# 10_BOOT.net
KiCad netlist of a schematic drawn in Altium Designer
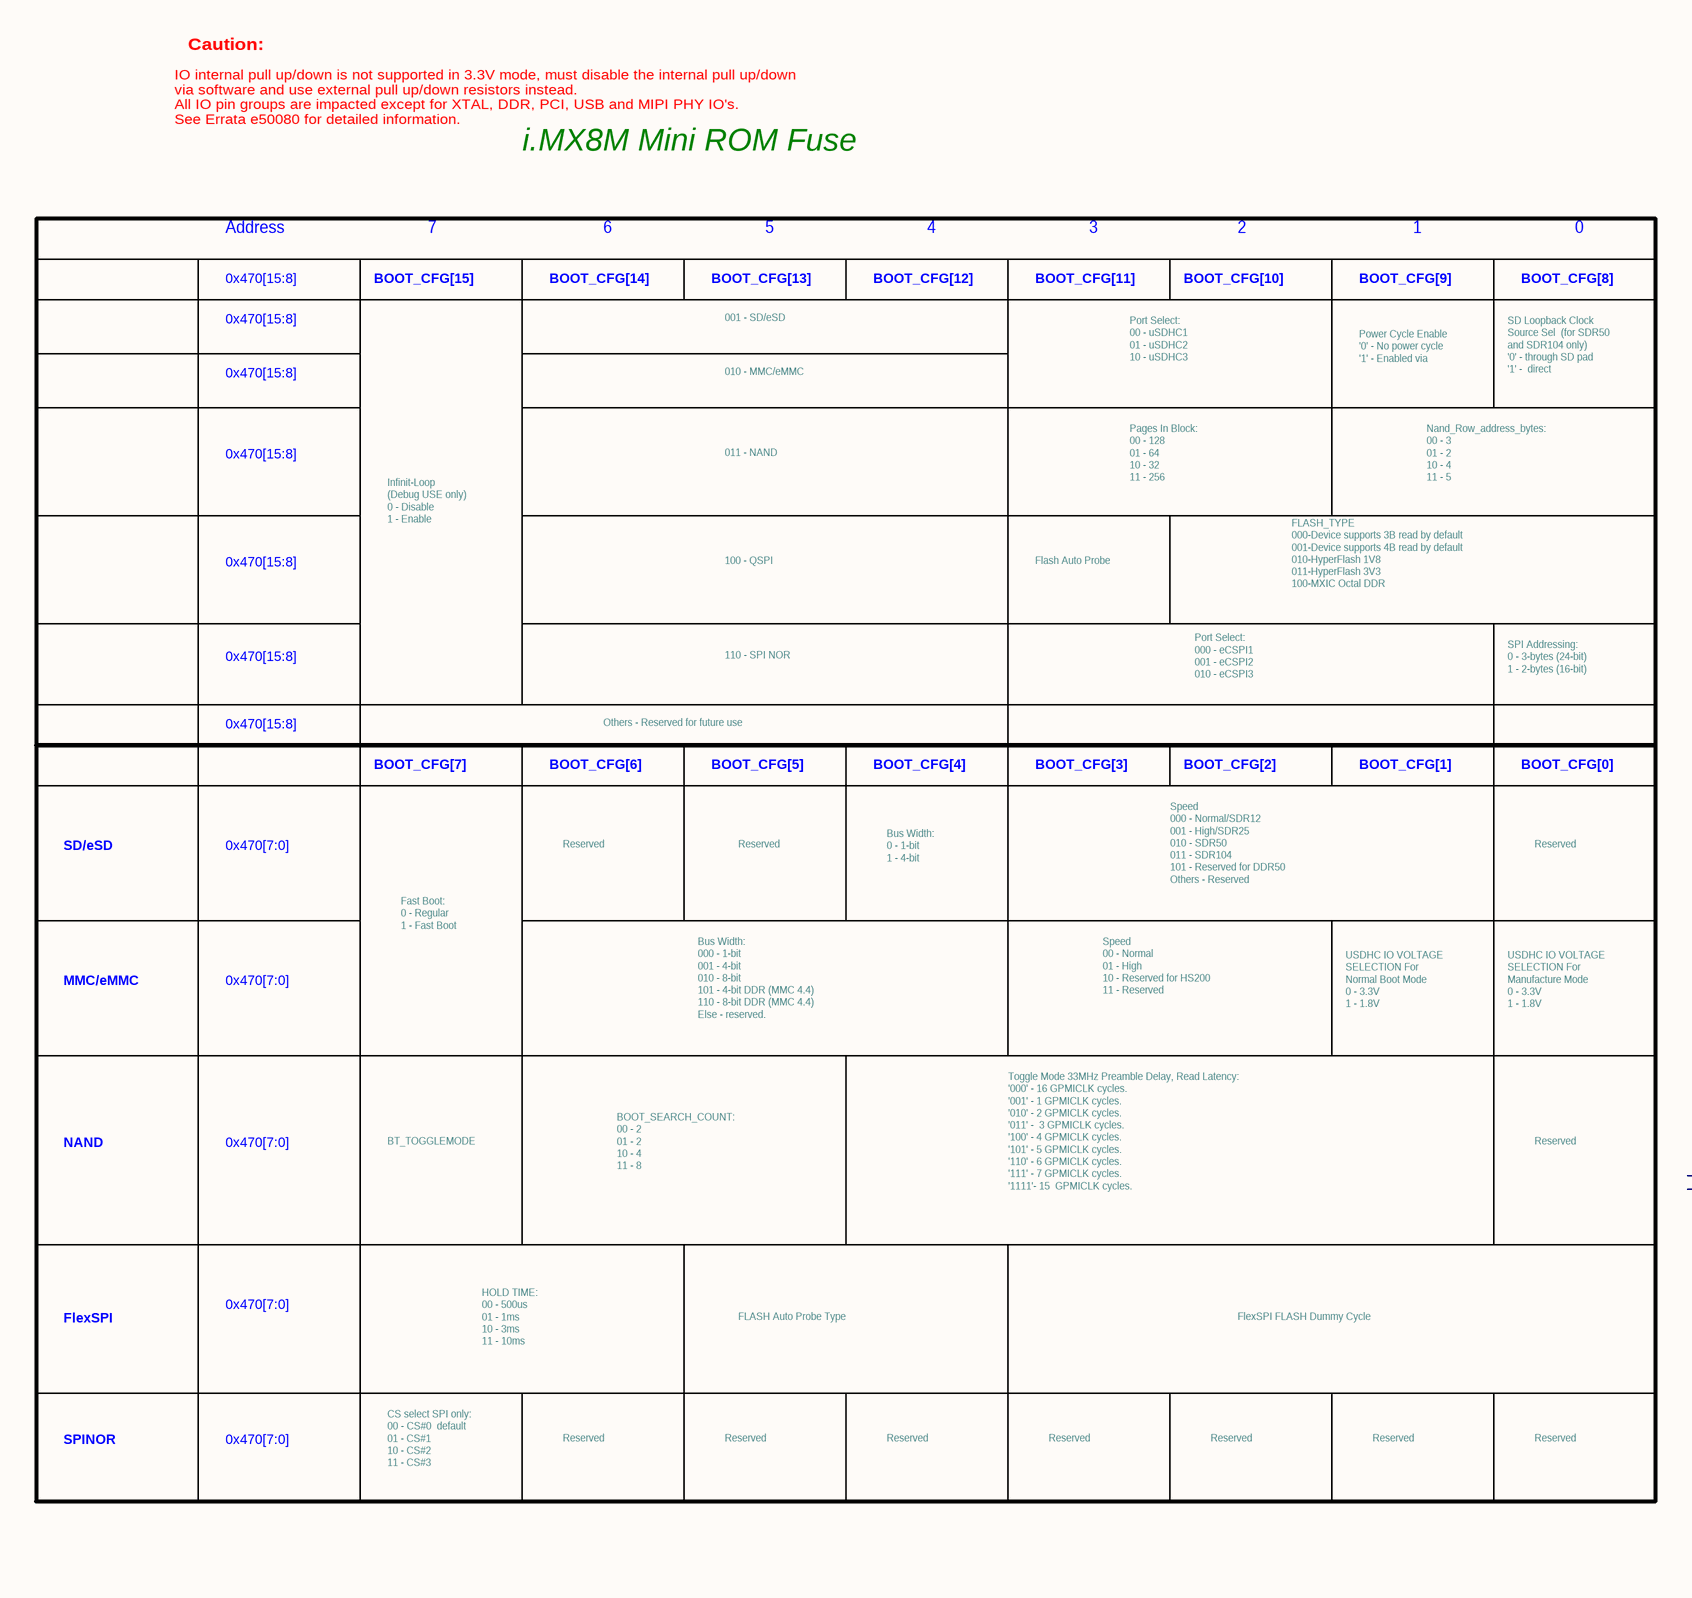
[diagram p0: 10 BOOT.SchDoc, left]
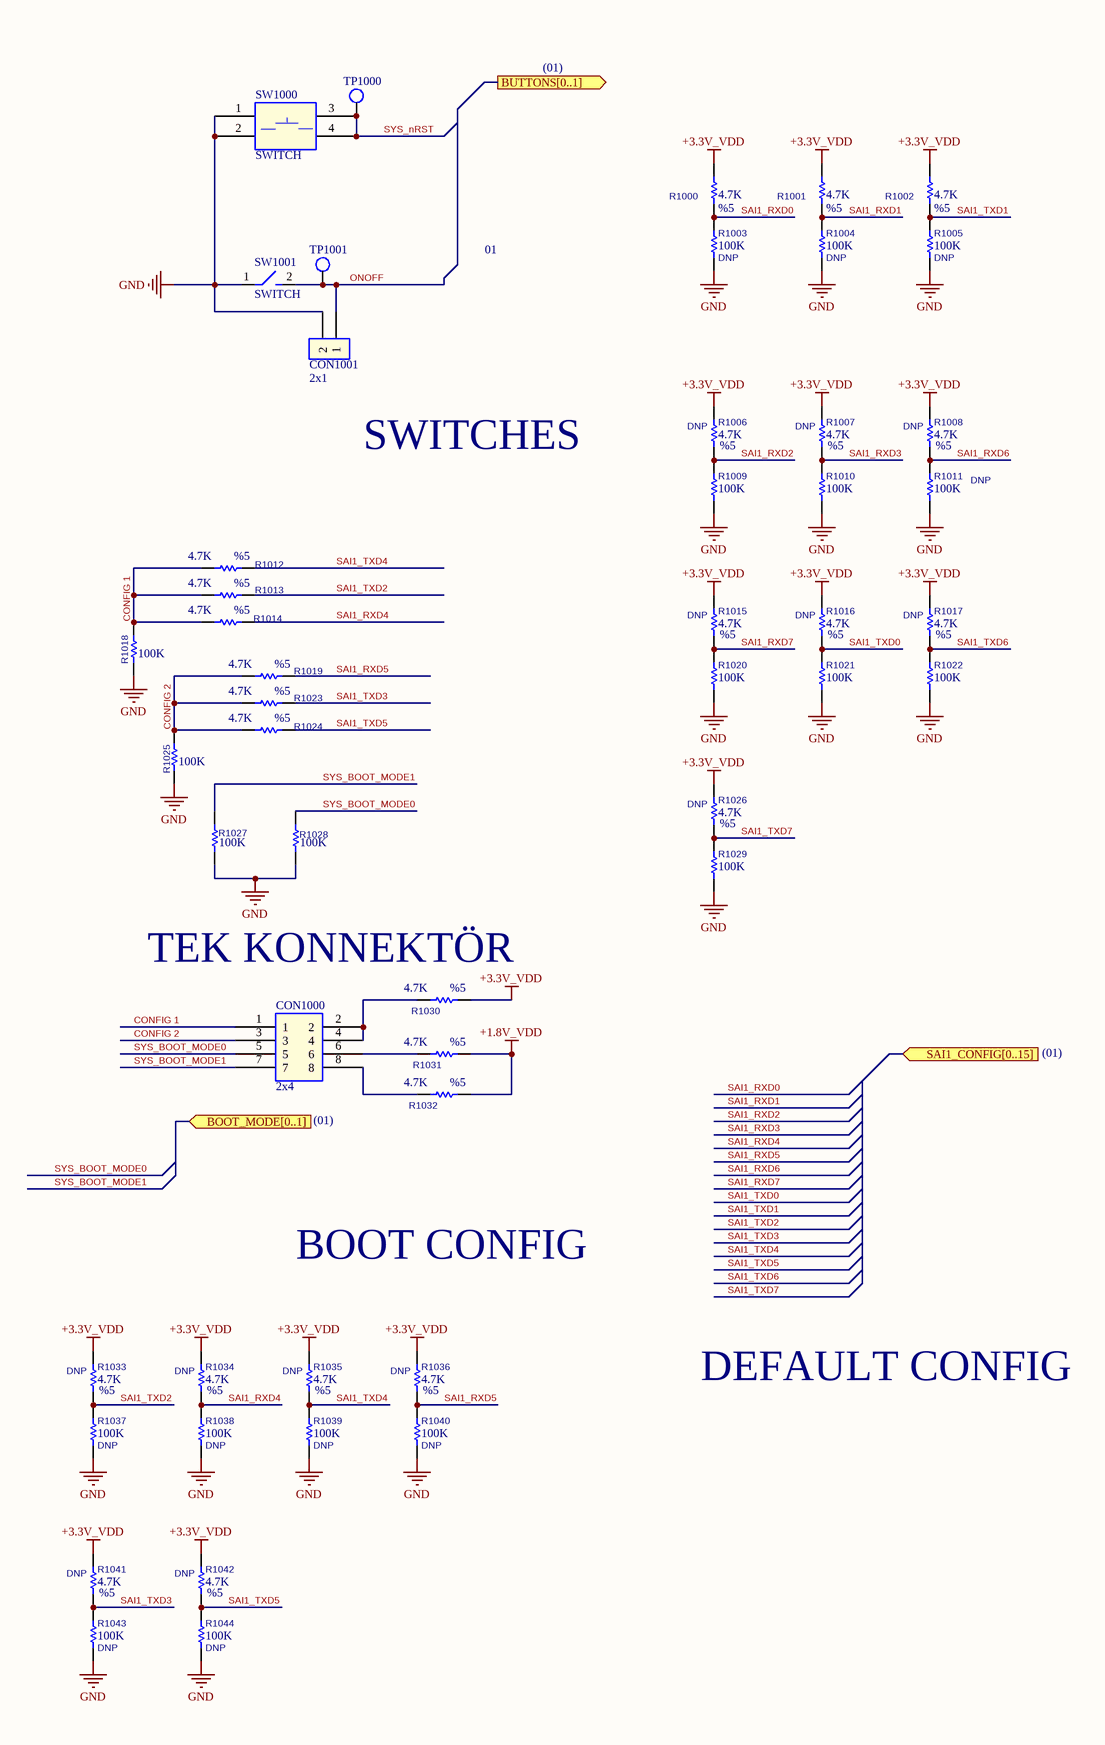
[diagram p1: 10 BOOT.SchDoc, right]

(export (version "E")
  (design (tool "Eeschema 10.0.6"))
  (components
    (comp (ref "CON1000")
      (value "2x4")
      (footprint "HEADER 2.54 X 4x2")
      (description "8 PIN 2.54MM HEADER")
      (fields (field (name "CREATED BY") "*") (field (name "CHECKED BY") "*"))
      (libsource (lib "ARETE_L") (part "CON-8 PIN 2.54MM"))
    )
    (comp (ref "CON1001")
      (value "2x1")
      (footprint "HEADER 1X2 2.54mm")
      (description "2 PIN 2.54 HEADER")
      (fields (field (name "CREATED BY") "*") (field (name "CHECKED BY") "*"))
      (libsource (lib "ARETE_V2_SCH") (part "CON-2 PIN 2.54"))
    )
    (comp (ref "R1000")
      (value "4.7K")
      (footprint "0402_RES")
      (description "RES 4.7K OHM 5% 1/16W 0402")
      (fields
        (field (name "TOLERANCE") "%5")
        (field (name "CREATED BY") "LA")
        (field (name "CHECKED BY") "*")
      )
      (libsource (lib "ARETE_SCH") (part "RES-4.7K"))
    )
    (comp (ref "R1001")
      (value "4.7K")
      (footprint "0402_RES")
      (description "RES 4.7K OHM 5% 1/16W 0402")
      (fields
        (field (name "TOLERANCE") "%5")
        (field (name "CREATED BY") "LA")
        (field (name "CHECKED BY") "*")
      )
      (libsource (lib "ARETE_SCH") (part "RES-4.7K"))
    )
    (comp (ref "R1002")
      (value "4.7K")
      (footprint "0402_RES")
      (description "RES 4.7K OHM 5% 1/16W 0402")
      (fields
        (field (name "TOLERANCE") "%5")
        (field (name "CREATED BY") "LA")
        (field (name "CHECKED BY") "*")
      )
      (libsource (lib "ARETE_SCH") (part "RES-4.7K"))
    )
    (comp (ref "R1003")
      (value "100K")
      (footprint "0402_RES")
      (description "RES 100K OHM 5% 1/16W 0402")
      (fields
        (field (name "ASSY_OPT") "DNP")
        (field (name "TOLERANCE") "%5")
        (field (name "CREATED BY") "LA")
        (field (name "CHECKED BY") "*")
      )
      (libsource (lib "ARETE_SCH") (part "RES-RMCF0402JT100K"))
    )
    (comp (ref "R1004")
      (value "100K")
      (footprint "0402_RES")
      (description "RES 100K OHM 5% 1/16W 0402")
      (fields
        (field (name "ASSY_OPT") "DNP")
        (field (name "TOLERANCE") "%5")
        (field (name "CREATED BY") "LA")
        (field (name "CHECKED BY") "*")
      )
      (libsource (lib "ARETE_SCH") (part "RES-RMCF0402JT100K"))
    )
    (comp (ref "R1005")
      (value "100K")
      (footprint "0402_RES")
      (description "RES 100K OHM 5% 1/16W 0402")
      (fields
        (field (name "ASSY_OPT") "DNP")
        (field (name "TOLERANCE") "%5")
        (field (name "CREATED BY") "LA")
        (field (name "CHECKED BY") "*")
      )
      (libsource (lib "ARETE_SCH") (part "RES-RMCF0402JT100K"))
    )
    (comp (ref "R1006")
      (value "4.7K")
      (footprint "0402_RES")
      (description "RES 4.7K OHM 5% 1/16W 0402")
      (fields
        (field (name "ASSY_OPT") "DNP")
        (field (name "TOLERANCE") "%5")
        (field (name "CREATED BY") "LA")
        (field (name "CHECKED BY") "*")
      )
      (libsource (lib "ARETE_SCH") (part "RES-4.7K"))
    )
    (comp (ref "R1007")
      (value "4.7K")
      (footprint "0402_RES")
      (description "RES 4.7K OHM 5% 1/16W 0402")
      (fields
        (field (name "ASSY_OPT") "DNP")
        (field (name "TOLERANCE") "%5")
        (field (name "CREATED BY") "LA")
        (field (name "CHECKED BY") "*")
      )
      (libsource (lib "ARETE_SCH") (part "RES-4.7K"))
    )
    (comp (ref "R1008")
      (value "4.7K")
      (footprint "0402_RES")
      (description "RES 4.7K OHM 5% 1/16W 0402")
      (fields
        (field (name "ASSY_OPT") "DNP")
        (field (name "TOLERANCE") "%5")
        (field (name "CREATED BY") "LA")
        (field (name "CHECKED BY") "*")
      )
      (libsource (lib "ARETE_SCH") (part "RES-4.7K"))
    )
    (comp (ref "R1009")
      (value "100K")
      (footprint "0402_RES")
      (description "RES 100K OHM 5% 1/16W 0402")
      (fields
        (field (name "TOLERANCE") "%5")
        (field (name "CREATED BY") "LA")
        (field (name "CHECKED BY") "*")
      )
      (libsource (lib "ARETE_SCH") (part "RES-RMCF0402JT100K"))
    )
    (comp (ref "R1010")
      (value "100K")
      (footprint "0402_RES")
      (description "RES 100K OHM 5% 1/16W 0402")
      (fields
        (field (name "TOLERANCE") "%5")
        (field (name "CREATED BY") "LA")
        (field (name "CHECKED BY") "*")
      )
      (libsource (lib "ARETE_SCH") (part "RES-RMCF0402JT100K"))
    )
    (comp (ref "R1011")
      (value "100K")
      (footprint "0402_RES")
      (description "RES 100K OHM 5% 1/16W 0402")
      (fields
        (field (name "ASSY_OPT") "DNP")
        (field (name "TOLERANCE") "%5")
        (field (name "CREATED BY") "LA")
        (field (name "CHECKED BY") "*")
      )
      (libsource (lib "ARETE_SCH") (part "RES-RMCF0402JT100K"))
    )
    (comp (ref "R1012")
      (value "4.7K")
      (footprint "0402_RES")
      (description "RES 4.7K OHM 5% 1/16W 0402")
      (fields
        (field (name "TOLERANCE") "%5")
        (field (name "CREATED BY") "LA")
        (field (name "CHECKED BY") "*")
      )
      (libsource (lib "ARETE_SCH") (part "RES-4.7K"))
    )
    (comp (ref "R1013")
      (value "4.7K")
      (footprint "0402_RES")
      (description "RES 4.7K OHM 5% 1/16W 0402")
      (fields
        (field (name "TOLERANCE") "%5")
        (field (name "CREATED BY") "LA")
        (field (name "CHECKED BY") "*")
      )
      (libsource (lib "ARETE_SCH") (part "RES-4.7K"))
    )
    (comp (ref "R1014")
      (value "4.7K")
      (footprint "0402_RES")
      (description "RES 4.7K OHM 5% 1/16W 0402")
      (fields
        (field (name "TOLERANCE") "%5")
        (field (name "CREATED BY") "LA")
        (field (name "CHECKED BY") "*")
      )
      (libsource (lib "ARETE_SCH") (part "RES-4.7K"))
    )
    (comp (ref "R1015")
      (value "4.7K")
      (footprint "0402_RES")
      (description "RES 4.7K OHM 5% 1/16W 0402")
      (fields
        (field (name "ASSY_OPT") "DNP")
        (field (name "TOLERANCE") "%5")
        (field (name "CREATED BY") "LA")
        (field (name "CHECKED BY") "*")
      )
      (libsource (lib "ARETE_SCH") (part "RES-4.7K"))
    )
    (comp (ref "R1016")
      (value "4.7K")
      (footprint "0402_RES")
      (description "RES 4.7K OHM 5% 1/16W 0402")
      (fields
        (field (name "ASSY_OPT") "DNP")
        (field (name "TOLERANCE") "%5")
        (field (name "CREATED BY") "LA")
        (field (name "CHECKED BY") "*")
      )
      (libsource (lib "ARETE_SCH") (part "RES-4.7K"))
    )
    (comp (ref "R1017")
      (value "4.7K")
      (footprint "0402_RES")
      (description "RES 4.7K OHM 5% 1/16W 0402")
      (fields
        (field (name "ASSY_OPT") "DNP")
        (field (name "TOLERANCE") "%5")
        (field (name "CREATED BY") "LA")
        (field (name "CHECKED BY") "*")
      )
      (libsource (lib "ARETE_SCH") (part "RES-4.7K"))
    )
    (comp (ref "R1018")
      (value "100K")
      (footprint "0402_RES")
      (description "RES 100K OHM 5% 1/16W 0402")
      (fields
        (field (name "TOLERANCE") "%5")
        (field (name "CREATED BY") "LA")
        (field (name "CHECKED BY") "*")
      )
      (libsource (lib "ARETE_SCH") (part "RES-RMCF0402JT100K"))
    )
    (comp (ref "R1019")
      (value "4.7K")
      (footprint "0402_RES")
      (description "RES 4.7K OHM 5% 1/16W 0402")
      (fields
        (field (name "TOLERANCE") "%5")
        (field (name "CREATED BY") "LA")
        (field (name "CHECKED BY") "*")
      )
      (libsource (lib "ARETE_SCH") (part "RES-4.7K"))
    )
    (comp (ref "R1020")
      (value "100K")
      (footprint "0402_RES")
      (description "RES 100K OHM 5% 1/16W 0402")
      (fields
        (field (name "TOLERANCE") "%5")
        (field (name "CREATED BY") "LA")
        (field (name "CHECKED BY") "*")
      )
      (libsource (lib "ARETE_SCH") (part "RES-RMCF0402JT100K"))
    )
    (comp (ref "R1021")
      (value "100K")
      (footprint "0402_RES")
      (description "RES 100K OHM 5% 1/16W 0402")
      (fields
        (field (name "TOLERANCE") "%5")
        (field (name "CREATED BY") "LA")
        (field (name "CHECKED BY") "*")
      )
      (libsource (lib "ARETE_SCH") (part "RES-RMCF0402JT100K"))
    )
    (comp (ref "R1022")
      (value "100K")
      (footprint "0402_RES")
      (description "RES 100K OHM 5% 1/16W 0402")
      (fields
        (field (name "TOLERANCE") "%5")
        (field (name "CREATED BY") "LA")
        (field (name "CHECKED BY") "*")
      )
      (libsource (lib "ARETE_SCH") (part "RES-RMCF0402JT100K"))
    )
    (comp (ref "R1023")
      (value "4.7K")
      (footprint "0402_RES")
      (description "RES 4.7K OHM 5% 1/16W 0402")
      (fields
        (field (name "TOLERANCE") "%5")
        (field (name "CREATED BY") "LA")
        (field (name "CHECKED BY") "*")
      )
      (libsource (lib "ARETE_SCH") (part "RES-4.7K"))
    )
    (comp (ref "R1024")
      (value "4.7K")
      (footprint "0402_RES")
      (description "RES 4.7K OHM 5% 1/16W 0402")
      (fields
        (field (name "TOLERANCE") "%5")
        (field (name "CREATED BY") "LA")
        (field (name "CHECKED BY") "*")
      )
      (libsource (lib "ARETE_SCH") (part "RES-4.7K"))
    )
    (comp (ref "R1025")
      (value "100K")
      (footprint "0402_RES")
      (description "RES 100K OHM 5% 1/16W 0402")
      (fields
        (field (name "TOLERANCE") "%5")
        (field (name "CREATED BY") "LA")
        (field (name "CHECKED BY") "*")
      )
      (libsource (lib "ARETE_SCH") (part "RES-RMCF0402JT100K"))
    )
    (comp (ref "R1026")
      (value "4.7K")
      (footprint "0402_RES")
      (description "RES 4.7K OHM 5% 1/16W 0402")
      (fields
        (field (name "ASSY_OPT") "DNP")
        (field (name "TOLERANCE") "%5")
        (field (name "CREATED BY") "LA")
        (field (name "CHECKED BY") "*")
      )
      (libsource (lib "ARETE_SCH") (part "RES-4.7K"))
    )
    (comp (ref "R1027")
      (value "100K")
      (footprint "0402_RES")
      (description "RES 100K OHM 5% 1/16W 0402")
      (fields
        (field (name "TOLERANCE") "%5")
        (field (name "CREATED BY") "LA")
        (field (name "CHECKED BY") "*")
      )
      (libsource (lib "ARETE_SCH") (part "RES-RMCF0402JT100K"))
    )
    (comp (ref "R1028")
      (value "100K")
      (footprint "0402_RES")
      (description "RES 100K OHM 5% 1/16W 0402")
      (fields
        (field (name "TOLERANCE") "%5")
        (field (name "CREATED BY") "LA")
        (field (name "CHECKED BY") "*")
      )
      (libsource (lib "ARETE_SCH") (part "RES-RMCF0402JT100K"))
    )
    (comp (ref "R1029")
      (value "100K")
      (footprint "0402_RES")
      (description "RES 100K OHM 5% 1/16W 0402")
      (fields
        (field (name "TOLERANCE") "%5")
        (field (name "CREATED BY") "LA")
        (field (name "CHECKED BY") "*")
      )
      (libsource (lib "ARETE_SCH") (part "RES-RMCF0402JT100K"))
    )
    (comp (ref "R1030")
      (value "4.7K")
      (footprint "0402_RES")
      (description "RES 4.7K OHM 5% 1/16W 0402")
      (fields
        (field (name "TOLERANCE") "%5")
        (field (name "CREATED BY") "LA")
        (field (name "CHECKED BY") "*")
      )
      (libsource (lib "ARETE_SCH") (part "RES-4.7K"))
    )
    (comp (ref "R1031")
      (value "4.7K")
      (footprint "0402_RES")
      (description "RES 4.7K OHM 5% 1/16W 0402")
      (fields
        (field (name "TOLERANCE") "%5")
        (field (name "CREATED BY") "LA")
        (field (name "CHECKED BY") "*")
      )
      (libsource (lib "ARETE_SCH") (part "RES-4.7K"))
    )
    (comp (ref "R1032")
      (value "4.7K")
      (footprint "0402_RES")
      (description "RES 4.7K OHM 5% 1/16W 0402")
      (fields
        (field (name "TOLERANCE") "%5")
        (field (name "CREATED BY") "LA")
        (field (name "CHECKED BY") "*")
      )
      (libsource (lib "ARETE_SCH") (part "RES-4.7K"))
    )
    (comp (ref "R1033")
      (value "4.7K")
      (footprint "0402_RES")
      (description "RES 4.7K OHM 5% 1/16W 0402")
      (fields
        (field (name "ASSY_OPT") "DNP")
        (field (name "TOLERANCE") "%5")
        (field (name "CREATED BY") "LA")
        (field (name "CHECKED BY") "*")
      )
      (libsource (lib "ARETE_SCH") (part "RES-4.7K"))
    )
    (comp (ref "R1034")
      (value "4.7K")
      (footprint "0402_RES")
      (description "RES 4.7K OHM 5% 1/16W 0402")
      (fields
        (field (name "ASSY_OPT") "DNP")
        (field (name "TOLERANCE") "%5")
        (field (name "CREATED BY") "LA")
        (field (name "CHECKED BY") "*")
      )
      (libsource (lib "ARETE_SCH") (part "RES-4.7K"))
    )
    (comp (ref "R1035")
      (value "4.7K")
      (footprint "0402_RES")
      (description "RES 4.7K OHM 5% 1/16W 0402")
      (fields
        (field (name "ASSY_OPT") "DNP")
        (field (name "TOLERANCE") "%5")
        (field (name "CREATED BY") "LA")
        (field (name "CHECKED BY") "*")
      )
      (libsource (lib "ARETE_SCH") (part "RES-4.7K"))
    )
    (comp (ref "R1036")
      (value "4.7K")
      (footprint "0402_RES")
      (description "RES 4.7K OHM 5% 1/16W 0402")
      (fields
        (field (name "ASSY_OPT") "DNP")
        (field (name "TOLERANCE") "%5")
        (field (name "CREATED BY") "LA")
        (field (name "CHECKED BY") "*")
      )
      (libsource (lib "ARETE_SCH") (part "RES-4.7K"))
    )
    (comp (ref "R1037")
      (value "100K")
      (footprint "0402_RES")
      (description "RES 100K OHM 5% 1/16W 0402")
      (fields
        (field (name "ASSY_OPT") "DNP")
        (field (name "TOLERANCE") "%5")
        (field (name "CREATED BY") "LA")
        (field (name "CHECKED BY") "*")
      )
      (libsource (lib "ARETE_SCH") (part "RES-RMCF0402JT100K"))
    )
    (comp (ref "R1038")
      (value "100K")
      (footprint "0402_RES")
      (description "RES 100K OHM 5% 1/16W 0402")
      (fields
        (field (name "ASSY_OPT") "DNP")
        (field (name "TOLERANCE") "%5")
        (field (name "CREATED BY") "LA")
        (field (name "CHECKED BY") "*")
      )
      (libsource (lib "ARETE_SCH") (part "RES-RMCF0402JT100K"))
    )
    (comp (ref "R1039")
      (value "100K")
      (footprint "0402_RES")
      (description "RES 100K OHM 5% 1/16W 0402")
      (fields
        (field (name "ASSY_OPT") "DNP")
        (field (name "TOLERANCE") "%5")
        (field (name "CREATED BY") "LA")
        (field (name "CHECKED BY") "*")
      )
      (libsource (lib "ARETE_SCH") (part "RES-RMCF0402JT100K"))
    )
    (comp (ref "R1040")
      (value "100K")
      (footprint "0402_RES")
      (description "RES 100K OHM 5% 1/16W 0402")
      (fields
        (field (name "ASSY_OPT") "DNP")
        (field (name "TOLERANCE") "%5")
        (field (name "CREATED BY") "LA")
        (field (name "CHECKED BY") "*")
      )
      (libsource (lib "ARETE_SCH") (part "RES-RMCF0402JT100K"))
    )
    (comp (ref "R1041")
      (value "4.7K")
      (footprint "0402_RES")
      (description "RES 4.7K OHM 5% 1/16W 0402")
      (fields
        (field (name "ASSY_OPT") "DNP")
        (field (name "TOLERANCE") "%5")
        (field (name "CREATED BY") "LA")
        (field (name "CHECKED BY") "*")
      )
      (libsource (lib "ARETE_SCH") (part "RES-4.7K"))
    )
    (comp (ref "R1042")
      (value "4.7K")
      (footprint "0402_RES")
      (description "RES 4.7K OHM 5% 1/16W 0402")
      (fields
        (field (name "ASSY_OPT") "DNP")
        (field (name "TOLERANCE") "%5")
        (field (name "CREATED BY") "LA")
        (field (name "CHECKED BY") "*")
      )
      (libsource (lib "ARETE_SCH") (part "RES-4.7K"))
    )
    (comp (ref "R1043")
      (value "100K")
      (footprint "0402_RES")
      (description "RES 100K OHM 5% 1/16W 0402")
      (fields
        (field (name "ASSY_OPT") "DNP")
        (field (name "TOLERANCE") "%5")
        (field (name "CREATED BY") "LA")
        (field (name "CHECKED BY") "*")
      )
      (libsource (lib "ARETE_SCH") (part "RES-RMCF0402JT100K"))
    )
    (comp (ref "R1044")
      (value "100K")
      (footprint "0402_RES")
      (description "RES 100K OHM 5% 1/16W 0402")
      (fields
        (field (name "ASSY_OPT") "DNP")
        (field (name "TOLERANCE") "%5")
        (field (name "CREATED BY") "LA")
        (field (name "CHECKED BY") "*")
      )
      (libsource (lib "ARETE_SCH") (part "RES-RMCF0402JT100K"))
    )
    (comp (ref "SW1000")
      (value "SWITCH")
      (footprint "BUTTON 6x6")
      (description "SWITCH TACT 6x6MM 8.5MM 160gf SMD")
      (fields (field (name "CREATED BY") "LA") (field (name "CHECKED BY") "*"))
      (libsource (lib "ARETE_SCH") (part "SW-DS1042-03-1-9-KKR-160-10"))
    )
    (comp (ref "SW1001")
      (value "SWITCH")
      (footprint "3.00mm x 2.00mm SWITCH")
      (description "SWITCH TACTILE, SPST-NO, 0.02A 1")
      (fields (field (name "CREATED BY") "EE") (field (name "CHECKED BY") "*"))
      (libsource (lib "ARETE_V2_SCH") (part "SW-STO-060A16AB"))
    )
    (comp (ref "TP1000")
      (value "TEST POINT 15")
      (footprint "testpoint_15")
      (libsource (lib "ARETE_L") (part "TEST POINT 15"))
    )
    (comp (ref "TP1001")
      (value "TEST POINT 15")
      (footprint "testpoint_15")
      (libsource (lib "ARETE_L") (part "TEST POINT 15"))
    )
  )
  (nets
    (net (code "21") (name "+1.8V_VDD") (class "Default")
      (node (ref "R1031") (pin "1") (pinfunction "1_1") (pintype "passive"))
      (node (ref "R1032") (pin "1") (pinfunction "1_1") (pintype "passive"))
    )
    (net (code "22") (name "+3.3V_VDD") (class "Default")
      (node (ref "R1000") (pin "2") (pinfunction "2_2") (pintype "passive"))
      (node (ref "R1001") (pin "2") (pinfunction "2_2") (pintype "passive"))
      (node (ref "R1002") (pin "2") (pinfunction "2_2") (pintype "passive"))
      (node (ref "R1006") (pin "2") (pinfunction "2_2") (pintype "passive"))
      (node (ref "R1007") (pin "2") (pinfunction "2_2") (pintype "passive"))
      (node (ref "R1008") (pin "2") (pinfunction "2_2") (pintype "passive"))
      (node (ref "R1015") (pin "2") (pinfunction "2_2") (pintype "passive"))
      (node (ref "R1016") (pin "2") (pinfunction "2_2") (pintype "passive"))
      (node (ref "R1017") (pin "2") (pinfunction "2_2") (pintype "passive"))
      (node (ref "R1026") (pin "2") (pinfunction "2_2") (pintype "passive"))
      (node (ref "R1030") (pin "1") (pinfunction "1_1") (pintype "passive"))
      (node (ref "R1033") (pin "2") (pinfunction "2_2") (pintype "passive"))
      (node (ref "R1034") (pin "2") (pinfunction "2_2") (pintype "passive"))
      (node (ref "R1035") (pin "2") (pinfunction "2_2") (pintype "passive"))
      (node (ref "R1036") (pin "2") (pinfunction "2_2") (pintype "passive"))
      (node (ref "R1041") (pin "2") (pinfunction "2_2") (pintype "passive"))
      (node (ref "R1042") (pin "2") (pinfunction "2_2") (pintype "passive"))
    )
    (net (code "25") (name "/CONFIG 1") (class "Default")
      (node (ref "CON1000") (pin "1") (pinfunction "1_1") (pintype "passive"))
      (node (ref "R1012") (pin "2") (pinfunction "2_2") (pintype "passive"))
      (node (ref "R1013") (pin "2") (pinfunction "2_2") (pintype "passive"))
      (node (ref "R1014") (pin "2") (pinfunction "2_2") (pintype "passive"))
      (node (ref "R1018") (pin "2") (pinfunction "2_2") (pintype "passive"))
    )
    (net (code "26") (name "/CONFIG 2") (class "Default")
      (node (ref "CON1000") (pin "3") (pinfunction "3_3") (pintype "passive"))
      (node (ref "R1019") (pin "2") (pinfunction "2_2") (pintype "passive"))
      (node (ref "R1023") (pin "2") (pinfunction "2_2") (pintype "passive"))
      (node (ref "R1024") (pin "2") (pinfunction "2_2") (pintype "passive"))
      (node (ref "R1025") (pin "2") (pinfunction "2_2") (pintype "passive"))
    )
    (net (code "27") (name "/ONOFF") (class "Default")
      (node (ref "CON1001") (pin "1") (pinfunction "1_1") (pintype "passive"))
      (node (ref "SW1001") (pin "2") (pinfunction "2_2") (pintype "passive"))
      (node (ref "TP1001") (pin "1") (pinfunction "1_1") (pintype "passive"))
    )
    (net (code "29") (name "/SAI1_RXD0") (class "Default")
      (node (ref "R1000") (pin "1") (pinfunction "1_1") (pintype "passive"))
      (node (ref "R1003") (pin "2") (pinfunction "2_2") (pintype "passive"))
    )
    (net (code "30") (name "/SAI1_RXD1") (class "Default")
      (node (ref "R1001") (pin "1") (pinfunction "1_1") (pintype "passive"))
      (node (ref "R1004") (pin "2") (pinfunction "2_2") (pintype "passive"))
    )
    (net (code "31") (name "/SAI1_RXD2") (class "Default")
      (node (ref "R1006") (pin "1") (pinfunction "1_1") (pintype "passive"))
      (node (ref "R1009") (pin "2") (pinfunction "2_2") (pintype "passive"))
    )
    (net (code "32") (name "/SAI1_RXD3") (class "Default")
      (node (ref "R1007") (pin "1") (pinfunction "1_1") (pintype "passive"))
      (node (ref "R1010") (pin "2") (pinfunction "2_2") (pintype "passive"))
    )
    (net (code "33") (name "/SAI1_RXD4") (class "Default")
      (node (ref "R1014") (pin "1") (pinfunction "1_1") (pintype "passive"))
      (node (ref "R1034") (pin "1") (pinfunction "1_1") (pintype "passive"))
      (node (ref "R1038") (pin "2") (pinfunction "2_2") (pintype "passive"))
    )
    (net (code "34") (name "/SAI1_RXD5") (class "Default")
      (node (ref "R1019") (pin "1") (pinfunction "1_1") (pintype "passive"))
      (node (ref "R1036") (pin "1") (pinfunction "1_1") (pintype "passive"))
      (node (ref "R1040") (pin "2") (pinfunction "2_2") (pintype "passive"))
    )
    (net (code "35") (name "/SAI1_RXD6") (class "Default")
      (node (ref "R1008") (pin "1") (pinfunction "1_1") (pintype "passive"))
      (node (ref "R1011") (pin "2") (pinfunction "2_2") (pintype "passive"))
    )
    (net (code "36") (name "/SAI1_RXD7") (class "Default")
      (node (ref "R1015") (pin "1") (pinfunction "1_1") (pintype "passive"))
      (node (ref "R1020") (pin "2") (pinfunction "2_2") (pintype "passive"))
    )
    (net (code "37") (name "/SAI1_TXD0") (class "Default")
      (node (ref "R1016") (pin "1") (pinfunction "1_1") (pintype "passive"))
      (node (ref "R1021") (pin "2") (pinfunction "2_2") (pintype "passive"))
    )
    (net (code "38") (name "/SAI1_TXD1") (class "Default")
      (node (ref "R1002") (pin "1") (pinfunction "1_1") (pintype "passive"))
      (node (ref "R1005") (pin "2") (pinfunction "2_2") (pintype "passive"))
    )
    (net (code "39") (name "/SAI1_TXD2") (class "Default")
      (node (ref "R1013") (pin "1") (pinfunction "1_1") (pintype "passive"))
      (node (ref "R1033") (pin "1") (pinfunction "1_1") (pintype "passive"))
      (node (ref "R1037") (pin "2") (pinfunction "2_2") (pintype "passive"))
    )
    (net (code "40") (name "/SAI1_TXD3") (class "Default")
      (node (ref "R1023") (pin "1") (pinfunction "1_1") (pintype "passive"))
      (node (ref "R1041") (pin "1") (pinfunction "1_1") (pintype "passive"))
      (node (ref "R1043") (pin "2") (pinfunction "2_2") (pintype "passive"))
    )
    (net (code "41") (name "/SAI1_TXD4") (class "Default")
      (node (ref "R1012") (pin "1") (pinfunction "1_1") (pintype "passive"))
      (node (ref "R1035") (pin "1") (pinfunction "1_1") (pintype "passive"))
      (node (ref "R1039") (pin "2") (pinfunction "2_2") (pintype "passive"))
    )
    (net (code "42") (name "/SAI1_TXD5") (class "Default")
      (node (ref "R1024") (pin "1") (pinfunction "1_1") (pintype "passive"))
      (node (ref "R1042") (pin "1") (pinfunction "1_1") (pintype "passive"))
      (node (ref "R1044") (pin "2") (pinfunction "2_2") (pintype "passive"))
    )
    (net (code "43") (name "/SAI1_TXD6") (class "Default")
      (node (ref "R1017") (pin "1") (pinfunction "1_1") (pintype "passive"))
      (node (ref "R1022") (pin "2") (pinfunction "2_2") (pintype "passive"))
    )
    (net (code "44") (name "/SAI1_TXD7") (class "Default")
      (node (ref "R1026") (pin "1") (pinfunction "1_1") (pintype "passive"))
      (node (ref "R1029") (pin "2") (pinfunction "2_2") (pintype "passive"))
    )
    (net (code "45") (name "/SYS_BOOT_MODE0") (class "Default")
      (node (ref "CON1000") (pin "5") (pinfunction "5_5") (pintype "passive"))
      (node (ref "R1028") (pin "2") (pinfunction "2_2") (pintype "passive"))
    )
    (net (code "46") (name "/SYS_BOOT_MODE1") (class "Default")
      (node (ref "CON1000") (pin "7") (pinfunction "7_7") (pintype "passive"))
      (node (ref "R1027") (pin "2") (pinfunction "2_2") (pintype "passive"))
    )
    (net (code "47") (name "/SYS_nRST") (class "Default")
      (node (ref "SW1000") (pin "3") (pinfunction "3_3") (pintype "passive"))
      (node (ref "SW1000") (pin "4") (pinfunction "4_4") (pintype "passive"))
      (node (ref "TP1000") (pin "1") (pinfunction "1_1") (pintype "passive"))
    )
    (net (code "48") (name "GND") (class "Default")
      (node (ref "CON1001") (pin "2") (pinfunction "2_2") (pintype "passive"))
      (node (ref "R1003") (pin "1") (pinfunction "1_1") (pintype "passive"))
      (node (ref "R1004") (pin "1") (pinfunction "1_1") (pintype "passive"))
      (node (ref "R1005") (pin "1") (pinfunction "1_1") (pintype "passive"))
      (node (ref "R1009") (pin "1") (pinfunction "1_1") (pintype "passive"))
      (node (ref "R1010") (pin "1") (pinfunction "1_1") (pintype "passive"))
      (node (ref "R1011") (pin "1") (pinfunction "1_1") (pintype "passive"))
      (node (ref "R1018") (pin "1") (pinfunction "1_1") (pintype "passive"))
      (node (ref "R1020") (pin "1") (pinfunction "1_1") (pintype "passive"))
      (node (ref "R1021") (pin "1") (pinfunction "1_1") (pintype "passive"))
      (node (ref "R1022") (pin "1") (pinfunction "1_1") (pintype "passive"))
      (node (ref "R1025") (pin "1") (pinfunction "1_1") (pintype "passive"))
      (node (ref "R1027") (pin "1") (pinfunction "1_1") (pintype "passive"))
      (node (ref "R1028") (pin "1") (pinfunction "1_1") (pintype "passive"))
      (node (ref "R1029") (pin "1") (pinfunction "1_1") (pintype "passive"))
      (node (ref "R1037") (pin "1") (pinfunction "1_1") (pintype "passive"))
      (node (ref "R1038") (pin "1") (pinfunction "1_1") (pintype "passive"))
      (node (ref "R1039") (pin "1") (pinfunction "1_1") (pintype "passive"))
      (node (ref "R1040") (pin "1") (pinfunction "1_1") (pintype "passive"))
      (node (ref "R1043") (pin "1") (pinfunction "1_1") (pintype "passive"))
      (node (ref "R1044") (pin "1") (pinfunction "1_1") (pintype "passive"))
      (node (ref "SW1000") (pin "1") (pinfunction "1_1") (pintype "passive"))
      (node (ref "SW1000") (pin "2") (pinfunction "2_2") (pintype "passive"))
      (node (ref "SW1001") (pin "1") (pinfunction "1_1") (pintype "passive"))
    )
    (net (code "49") (name "Net-(CON1000-Pad2)") (class "Default")
      (node (ref "CON1000") (pin "2") (pinfunction "2_2") (pintype "passive"))
      (node (ref "CON1000") (pin "4") (pinfunction "4_4") (pintype "passive"))
      (node (ref "R1030") (pin "2") (pinfunction "2_2") (pintype "passive"))
    )
    (net (code "50") (name "Net-(CON1000-Pad6)") (class "Default")
      (node (ref "CON1000") (pin "6") (pinfunction "6_6") (pintype "passive"))
      (node (ref "R1031") (pin "2") (pinfunction "2_2") (pintype "passive"))
    )
    (net (code "51") (name "Net-(CON1000-Pad8)") (class "Default")
      (node (ref "CON1000") (pin "8") (pinfunction "8_8") (pintype "passive"))
      (node (ref "R1032") (pin "2") (pinfunction "2_2") (pintype "passive"))
    )
  )
)
